# IF_amplifier_MC1350.net
KiCad netlist of a schematic drawn in EAGLE
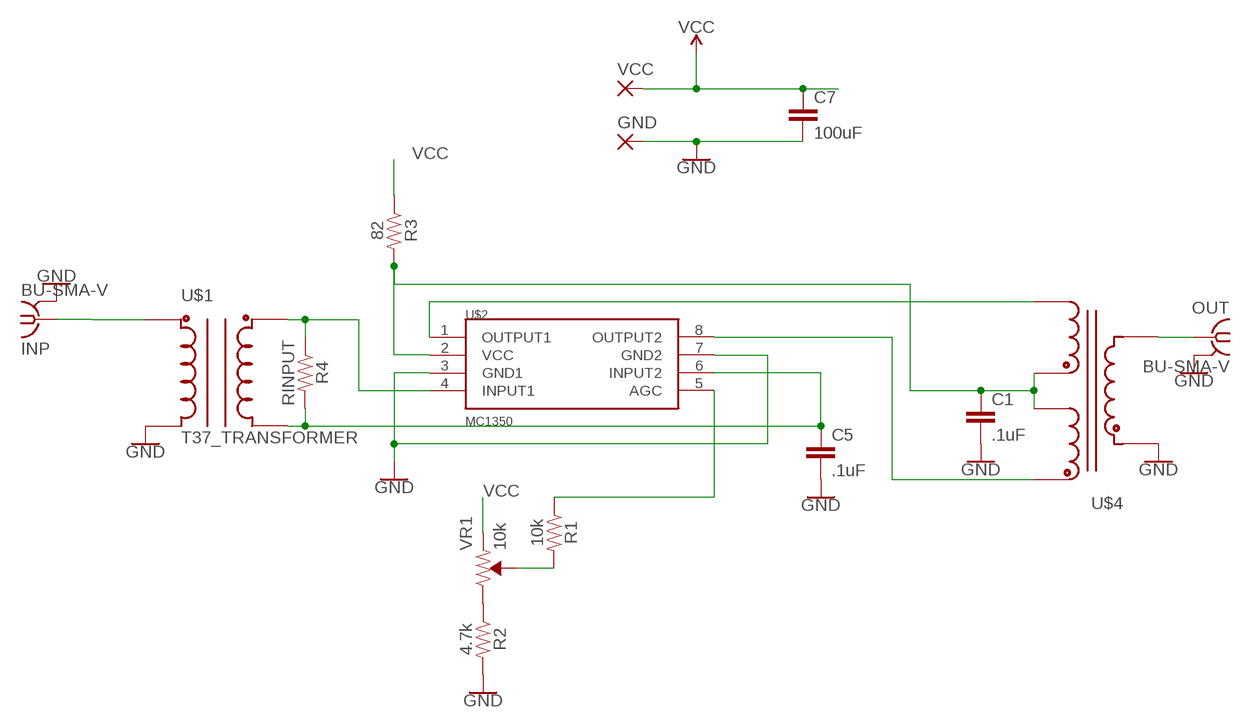
[diagram p0: schematic, sheet 1]

(export (version "E")
  (design (tool "Eeschema 10.0.6"))
  (components
    (comp (ref "C1")
      (value ".1uF")
      (footprint "eagle-import:C5B3.5")
      (libsource (lib "eagle-import") (part "C5/3.5"))
    )
    (comp (ref "C5")
      (value ".1uF")
      (footprint "eagle-import:C5B3.5")
      (libsource (lib "eagle-import") (part "C5/3.5"))
    )
    (comp (ref "C7")
      (value "100uF")
      (footprint "eagle-import:C5B3.5")
      (libsource (lib "eagle-import") (part "C5/3.5"))
    )
    (comp (ref "GND")
      (value "3,17/1,1")
      (footprint "eagle-import:3,17_1,1")
      (libsource (lib "eagle-import") (part "3,17/1,1"))
    )
    (comp (ref "INP")
      (value "BU-SMA-V")
      (footprint "eagle-import:BU-SMA-V")
      (libsource (lib "eagle-import") (part "BU-SMA-V"))
    )
    (comp (ref "OUT")
      (value "BU-SMA-V")
      (footprint "eagle-import:BU-SMA-V")
      (libsource (lib "eagle-import") (part "BU-SMA-V"))
    )
    (comp (ref "R1")
      (value "10k")
      (footprint "eagle-import:AXIAL-0.3")
      (libsource (lib "eagle-import") (part "1KOHM-HORIZ-1/4W-1%"))
    )
    (comp (ref "R2")
      (value "4.7k")
      (footprint "eagle-import:AXIAL-0.3")
      (libsource (lib "eagle-import") (part "1KOHM-HORIZ-1/4W-1%"))
    )
    (comp (ref "R3")
      (value "82")
      (footprint "eagle-import:AXIAL-0.3")
      (libsource (lib "eagle-import") (part "1KOHM-HORIZ-1/4W-1%"))
    )
    (comp (ref "R4")
      (value "RINPUT")
      (footprint "eagle-import:AXIAL-0.3")
      (libsource (lib "eagle-import") (part "1KOHM-HORIZ-1/4W-1%"))
    )
    (comp (ref "U$1")
      (value "T37_TRANSFORMER")
      (footprint "eagle-import:T37_TRANSFORMER")
      (libsource (lib "eagle-import") (part "T37_TRANSFORMER"))
    )
    (comp (ref "U$2")
      (value "MC1350")
      (footprint "eagle-import:DIP8")
      (libsource (lib "eagle-import") (part "MC1350"))
    )
    (comp (ref "U$4")
      (value "T50_SPLITTER")
      (footprint "eagle-import:T50_SPLITTER")
      (libsource (lib "eagle-import") (part "T50_SPLITTER"))
    )
    (comp (ref "VCC")
      (value "3,17/1,1")
      (footprint "eagle-import:3,17_1,1")
      (libsource (lib "eagle-import") (part "3,17/1,1"))
    )
    (comp (ref "VR1")
      (value "10k")
      (footprint "eagle-import:TRIMPOT-PTH-3386U")
      (libsource (lib "eagle-import") (part "TRIMPOT-PTH-10MM-KNOB-1/2W-10%"))
    )
  )
  (nets
    (net (code "1") (name "GND") (class "Default")
      (node (ref "C1") (pin "2") (pinfunction "2_2") (pintype "passive"))
      (node (ref "C5") (pin "2") (pinfunction "2_2") (pintype "passive"))
      (node (ref "C7") (pin "2") (pinfunction "2_2") (pintype "passive"))
      (node (ref "GND") (pin "1") (pinfunction "P_1") (pintype "passive"))
      (node (ref "INP") (pin "2") (pinfunction "2_2") (pintype "passive"))
      (node (ref "INP") (pin "3") (pinfunction "2_3") (pintype "passive"))
      (node (ref "INP") (pin "4") (pinfunction "2_4") (pintype "passive"))
      (node (ref "INP") (pin "5") (pinfunction "2_5") (pintype "passive"))
      (node (ref "OUT") (pin "2") (pinfunction "2_2") (pintype "passive"))
      (node (ref "OUT") (pin "3") (pinfunction "2_3") (pintype "passive"))
      (node (ref "OUT") (pin "4") (pinfunction "2_4") (pintype "passive"))
      (node (ref "OUT") (pin "5") (pinfunction "2_5") (pintype "passive"))
      (node (ref "R2") (pin "P$2") (pinfunction "2_P$2") (pintype "passive"))
      (node (ref "U$1") (pin "C1A") (pinfunction "C1A_C1A") (pintype "bidirectional"))
      (node (ref "U$2") (pin "3") (pinfunction "GND1_3") (pintype "bidirectional"))
      (node (ref "U$2") (pin "7") (pinfunction "GND2_7") (pintype "bidirectional"))
      (node (ref "U$4") (pin "C1B") (pinfunction "C1B_C1B") (pintype "bidirectional"))
    )
    (net (code "2") (name "Net-(INP-Pad1)") (class "Default")
      (node (ref "INP") (pin "1") (pinfunction "1_1") (pintype "passive"))
      (node (ref "U$1") (pin "C1B") (pinfunction "C1B_C1B") (pintype "bidirectional"))
    )
    (net (code "3") (name "Net-(OUT-Pad1)") (class "Default")
      (node (ref "OUT") (pin "1") (pinfunction "1_1") (pintype "passive"))
      (node (ref "U$4") (pin "C1A") (pinfunction "C1A_C1A") (pintype "bidirectional"))
    )
    (net (code "4") (name "Net-(R1-1)") (class "Default")
      (node (ref "R1") (pin "P$1") (pinfunction "1_P$1") (pintype "passive"))
      (node (ref "U$2") (pin "5") (pinfunction "AGC_5") (pintype "bidirectional"))
    )
    (net (code "5") (name "Net-(R1-2)") (class "Default")
      (node (ref "R1") (pin "P$2") (pinfunction "2_P$2") (pintype "passive"))
      (node (ref "VR1") (pin "2") (pinfunction "WIPER_2") (pintype "passive"))
    )
    (net (code "6") (name "Net-(R2-1)") (class "Default")
      (node (ref "R2") (pin "P$1") (pinfunction "1_P$1") (pintype "passive"))
      (node (ref "VR1") (pin "3") (pinfunction "CW_3") (pintype "passive"))
    )
    (net (code "7") (name "Net-(R3-2)") (class "Default")
      (node (ref "C1") (pin "1") (pinfunction "1_1") (pintype "passive"))
      (node (ref "R3") (pin "P$2") (pinfunction "2_P$2") (pintype "passive"))
      (node (ref "U$2") (pin "2") (pinfunction "VCC_2") (pintype "bidirectional"))
      (node (ref "U$4") (pin "C2A") (pinfunction "C3B_C2A") (pintype "bidirectional"))
      (node (ref "U$4") (pin "C3A") (pinfunction "C2A_C3A") (pintype "bidirectional"))
    )
    (net (code "8") (name "Net-(R4-1)") (class "Default")
      (node (ref "R4") (pin "P$1") (pinfunction "1_P$1") (pintype "passive"))
      (node (ref "U$1") (pin "C2B") (pinfunction "C2B_C2B") (pintype "bidirectional"))
      (node (ref "U$2") (pin "4") (pinfunction "INPUT1_4") (pintype "bidirectional"))
    )
    (net (code "9") (name "Net-(R4-2)") (class "Default")
      (node (ref "C5") (pin "1") (pinfunction "1_1") (pintype "passive"))
      (node (ref "R4") (pin "P$2") (pinfunction "2_P$2") (pintype "passive"))
      (node (ref "U$1") (pin "C2A") (pinfunction "C2A_C2A") (pintype "bidirectional"))
      (node (ref "U$2") (pin "6") (pinfunction "INPUT2_6") (pintype "bidirectional"))
    )
    (net (code "10") (name "Net-(U$2-OUTPUT1)") (class "Default")
      (node (ref "U$2") (pin "1") (pinfunction "OUTPUT1_1") (pintype "bidirectional"))
      (node (ref "U$4") (pin "C2B") (pinfunction "C3A_C2B") (pintype "bidirectional"))
    )
    (net (code "11") (name "Net-(U$2-OUTPUT2)") (class "Default")
      (node (ref "U$2") (pin "8") (pinfunction "OUTPUT2_8") (pintype "bidirectional"))
      (node (ref "U$4") (pin "C3B") (pinfunction "C2B_C3B") (pintype "bidirectional"))
    )
    (net (code "12") (name "VCC") (class "Default")
      (node (ref "C7") (pin "1") (pinfunction "1_1") (pintype "passive"))
      (node (ref "R3") (pin "P$1") (pinfunction "1_P$1") (pintype "passive"))
      (node (ref "VCC") (pin "1") (pinfunction "P_1") (pintype "passive"))
      (node (ref "VR1") (pin "1") (pinfunction "CCW_1") (pintype "passive"))
    )
  )
)
